# interface.net
KiCad netlist of a schematic drawn in EAGLE
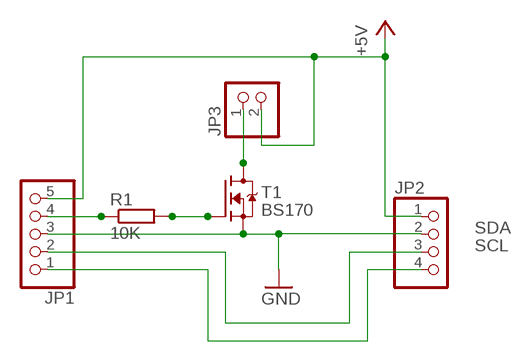
[diagram p0: schematic, sheet 1]

(export (version "E")
  (design (tool "Eeschema 10.0.6"))
  (components
    (comp (ref "JP1")
      (value "PINHD-1X5")
      (footprint "eagle-import:1X05")
      (libsource (lib "eagle-import") (part "PINHD-1X5"))
    )
    (comp (ref "JP2")
      (value "PINHD-1X4")
      (footprint "eagle-import:1X04")
      (libsource (lib "eagle-import") (part "PINHD-1X4"))
    )
    (comp (ref "JP3")
      (value "PINHD-1X2")
      (footprint "eagle-import:1X02")
      (libsource (lib "eagle-import") (part "PINHD-1X2"))
    )
    (comp (ref "R1")
      (value "10K")
      (footprint "eagle-import:R0805")
      (libsource (lib "eagle-import") (part "R-EU_R0805"))
    )
    (comp (ref "T1")
      (value "BS170")
      (footprint "eagle-import:SOT23")
      (libsource (lib "eagle-import") (part "MOSFET-N-SOT23"))
    )
  )
  (nets
    (net (code "1") (name "+5V") (class "Default")
      (node (ref "JP1") (pin "5") (pinfunction "5_5") (pintype "passive"))
      (node (ref "JP2") (pin "1") (pinfunction "1_1") (pintype "passive"))
      (node (ref "JP3") (pin "2") (pinfunction "2_2") (pintype "passive"))
    )
    (net (code "2") (name "GND") (class "Default")
      (node (ref "JP1") (pin "3") (pinfunction "3_3") (pintype "passive"))
      (node (ref "JP2") (pin "2") (pinfunction "2_2") (pintype "passive"))
      (node (ref "T1") (pin "2") (pinfunction "S_2") (pintype "passive"))
    )
    (net (code "3") (name "Net-(JP1-Pad1)") (class "Default")
      (node (ref "JP1") (pin "1") (pinfunction "1_1") (pintype "passive"))
      (node (ref "JP2") (pin "4") (pinfunction "4_4") (pintype "passive"))
    )
    (net (code "4") (name "Net-(JP1-Pad2)") (class "Default")
      (node (ref "JP1") (pin "2") (pinfunction "2_2") (pintype "passive"))
      (node (ref "JP2") (pin "3") (pinfunction "3_3") (pintype "passive"))
    )
    (net (code "5") (name "Net-(JP1-Pad4)") (class "Default")
      (node (ref "JP1") (pin "4") (pinfunction "4_4") (pintype "passive"))
      (node (ref "R1") (pin "1") (pinfunction "1_1") (pintype "passive"))
    )
    (net (code "6") (name "Net-(T1-D)") (class "Default")
      (node (ref "JP3") (pin "1") (pinfunction "1_1") (pintype "passive"))
      (node (ref "T1") (pin "3") (pinfunction "D_3") (pintype "passive"))
    )
    (net (code "7") (name "Net-(T1-G)") (class "Default")
      (node (ref "R1") (pin "2") (pinfunction "2_2") (pintype "passive"))
      (node (ref "T1") (pin "1") (pinfunction "G_1") (pintype "passive"))
    )
  )
)
